# ps2_cpld_kbd.net
KiCad netlist of a schematic drawn in EAGLE
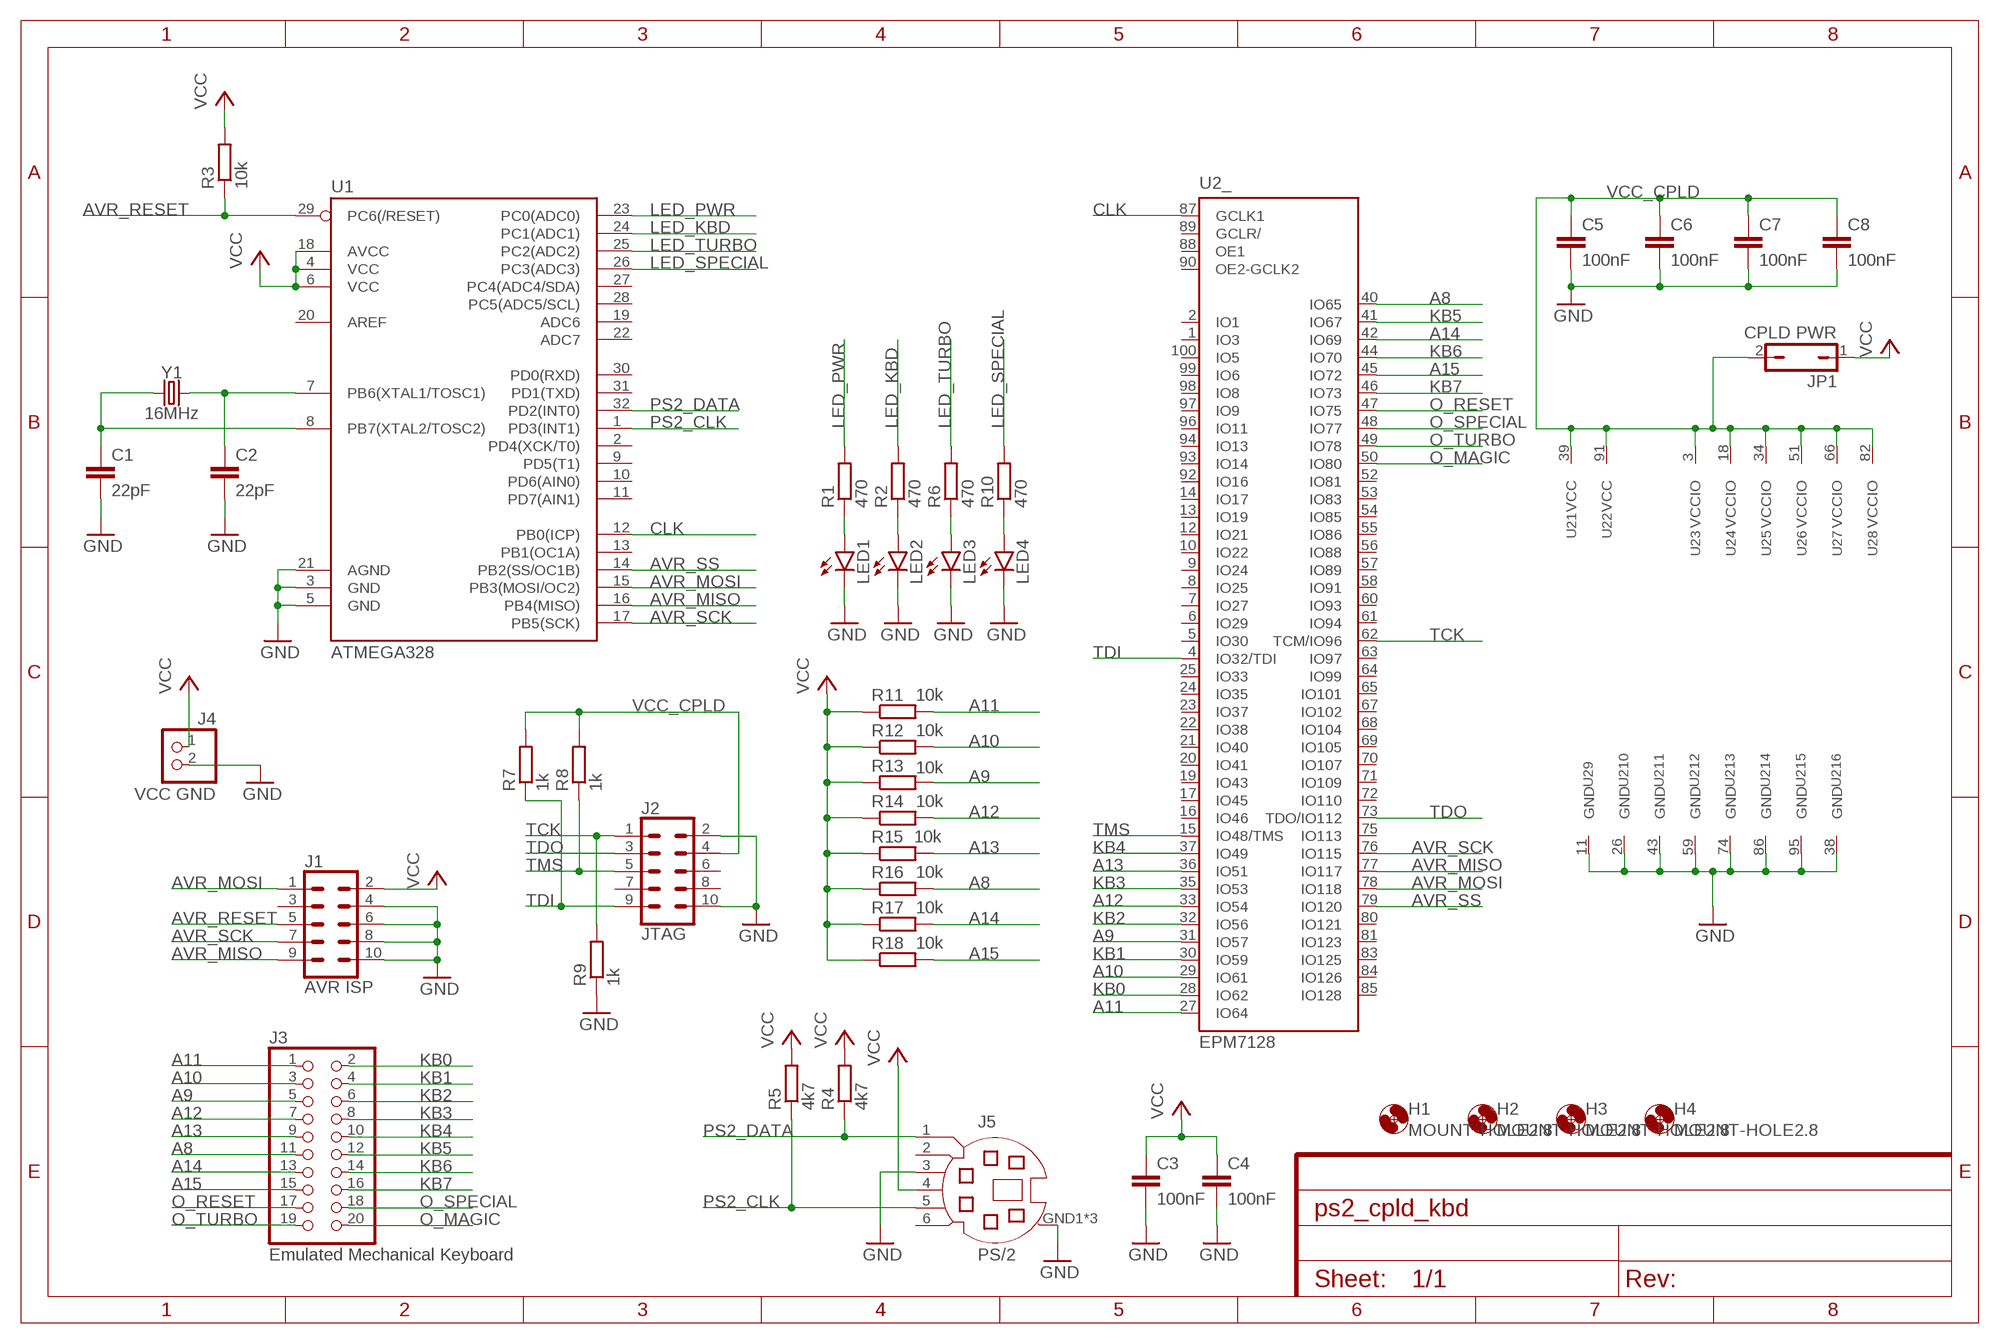
[diagram p0: schematic, sheet 1]

(export (version "E")
  (design (tool "Eeschema 10.0.6"))
  (components
    (comp (ref "C1")
      (value "22pF")
      (footprint "eagle-import:C0805K")
      (libsource (lib "eagle-import") (part "C-EUC0805K"))
    )
    (comp (ref "C2")
      (value "22pF")
      (footprint "eagle-import:C0805K")
      (libsource (lib "eagle-import") (part "C-EUC0805K"))
    )
    (comp (ref "C3")
      (value "100nF")
      (footprint "eagle-import:C0805K")
      (libsource (lib "eagle-import") (part "C-EUC0805K"))
    )
    (comp (ref "C4")
      (value "100nF")
      (footprint "eagle-import:C0805K")
      (libsource (lib "eagle-import") (part "C-EUC0805K"))
    )
    (comp (ref "C5")
      (value "100nF")
      (footprint "eagle-import:C0805K")
      (libsource (lib "eagle-import") (part "C-EUC0805K"))
    )
    (comp (ref "C6")
      (value "100nF")
      (footprint "eagle-import:C0805K")
      (libsource (lib "eagle-import") (part "C-EUC0805K"))
    )
    (comp (ref "C7")
      (value "100nF")
      (footprint "eagle-import:C0805K")
      (libsource (lib "eagle-import") (part "C-EUC0805K"))
    )
    (comp (ref "C8")
      (value "100nF")
      (footprint "eagle-import:C0805K")
      (libsource (lib "eagle-import") (part "C-EUC0805K"))
    )
    (comp (ref "H1")
      (value "MOUNT-HOLE2.8")
      (footprint "eagle-import:2,8")
      (libsource (lib "eagle-import") (part "MOUNT-HOLE2.8"))
    )
    (comp (ref "H2")
      (value "MOUNT-HOLE2.8")
      (footprint "eagle-import:2,8")
      (libsource (lib "eagle-import") (part "MOUNT-HOLE2.8"))
    )
    (comp (ref "H3")
      (value "MOUNT-HOLE2.8")
      (footprint "eagle-import:2,8")
      (libsource (lib "eagle-import") (part "MOUNT-HOLE2.8"))
    )
    (comp (ref "H4")
      (value "MOUNT-HOLE2.8")
      (footprint "eagle-import:2,8")
      (libsource (lib "eagle-import") (part "MOUNT-HOLE2.8"))
    )
    (comp (ref "J1")
      (value "AVR ISP")
      (footprint "eagle-import:2X5-SHROUDED_LOCK")
      (libsource (lib "eagle-import") (part "CONN_05X2SHD_LOCK"))
    )
    (comp (ref "J2")
      (value "JTAG")
      (footprint "eagle-import:2X5-SHROUDED_LOCK")
      (libsource (lib "eagle-import") (part "CONN_05X2SHD_LOCK"))
    )
    (comp (ref "J3")
      (value "Emulated Mechanical Keyboard")
      (footprint "eagle-import:2X10")
      (libsource (lib "eagle-import") (part "PINHD-2X10"))
    )
    (comp (ref "J4")
      (value "VCC GND")
      (footprint "eagle-import:1X02")
      (libsource (lib "eagle-import") (part "PINHD-1X2"))
    )
    (comp (ref "J5")
      (value "PS/2")
      (footprint "eagle-import:MDIN06SS")
      (libsource (lib "eagle-import") (part "MD06SS"))
    )
    (comp (ref "JP1")
      (value "CPLD PWR")
      (footprint "eagle-import:JP1")
      (libsource (lib "eagle-import") (part "JP1Q"))
    )
    (comp (ref "LED1")
      (value "LEDCHIPLED_0805")
      (footprint "eagle-import:CHIPLED_0805")
      (libsource (lib "eagle-import") (part "LEDCHIPLED_0805"))
    )
    (comp (ref "LED2")
      (value "LEDCHIPLED_0805")
      (footprint "eagle-import:CHIPLED_0805")
      (libsource (lib "eagle-import") (part "LEDCHIPLED_0805"))
    )
    (comp (ref "LED3")
      (value "LEDCHIPLED_0805")
      (footprint "eagle-import:CHIPLED_0805")
      (libsource (lib "eagle-import") (part "LEDCHIPLED_0805"))
    )
    (comp (ref "LED4")
      (value "LEDCHIPLED_0805")
      (footprint "eagle-import:CHIPLED_0805")
      (libsource (lib "eagle-import") (part "LEDCHIPLED_0805"))
    )
    (comp (ref "R1")
      (value "470")
      (footprint "eagle-import:R0805")
      (libsource (lib "eagle-import") (part "R-EU_R0805"))
    )
    (comp (ref "R2")
      (value "470")
      (footprint "eagle-import:R0805")
      (libsource (lib "eagle-import") (part "R-EU_R0805"))
    )
    (comp (ref "R3")
      (value "10k")
      (footprint "eagle-import:R0805")
      (libsource (lib "eagle-import") (part "R-EU_R0805"))
    )
    (comp (ref "R4")
      (value "4k7")
      (footprint "eagle-import:R0805")
      (libsource (lib "eagle-import") (part "R-EU_R0805"))
    )
    (comp (ref "R5")
      (value "4k7")
      (footprint "eagle-import:R0805")
      (libsource (lib "eagle-import") (part "R-EU_R0805"))
    )
    (comp (ref "R6")
      (value "470")
      (footprint "eagle-import:R0805")
      (libsource (lib "eagle-import") (part "R-EU_R0805"))
    )
    (comp (ref "R7")
      (value "1k")
      (footprint "eagle-import:R0805")
      (libsource (lib "eagle-import") (part "R-EU_R0805"))
    )
    (comp (ref "R8")
      (value "1k")
      (footprint "eagle-import:R0805")
      (libsource (lib "eagle-import") (part "R-EU_R0805"))
    )
    (comp (ref "R9")
      (value "1k")
      (footprint "eagle-import:R0805")
      (libsource (lib "eagle-import") (part "R-EU_R0805"))
    )
    (comp (ref "R10")
      (value "470")
      (footprint "eagle-import:R0805")
      (libsource (lib "eagle-import") (part "R-EU_R0805"))
    )
    (comp (ref "R11")
      (value "10k")
      (footprint "eagle-import:R0805")
      (libsource (lib "eagle-import") (part "R-EU_R0805"))
    )
    (comp (ref "R12")
      (value "10k")
      (footprint "eagle-import:R0805")
      (libsource (lib "eagle-import") (part "R-EU_R0805"))
    )
    (comp (ref "R13")
      (value "10k")
      (footprint "eagle-import:R0805")
      (libsource (lib "eagle-import") (part "R-EU_R0805"))
    )
    (comp (ref "R14")
      (value "10k")
      (footprint "eagle-import:R0805")
      (libsource (lib "eagle-import") (part "R-EU_R0805"))
    )
    (comp (ref "R15")
      (value "10k")
      (footprint "eagle-import:R0805")
      (libsource (lib "eagle-import") (part "R-EU_R0805"))
    )
    (comp (ref "R16")
      (value "10k")
      (footprint "eagle-import:R0805")
      (libsource (lib "eagle-import") (part "R-EU_R0805"))
    )
    (comp (ref "R17")
      (value "10k")
      (footprint "eagle-import:R0805")
      (libsource (lib "eagle-import") (part "R-EU_R0805"))
    )
    (comp (ref "R18")
      (value "10k")
      (footprint "eagle-import:R0805")
      (libsource (lib "eagle-import") (part "R-EU_R0805"))
    )
    (comp (ref "U1")
      (value "ATMEGA328")
      (footprint "eagle-import:TQFP32-08")
      (libsource (lib "eagle-import") (part "ATMEGA328P_TQFP"))
    )
    (comp (ref "U2")
      (value "EPM7128")
      (footprint "eagle-import:TQFP100")
      (fields (field (name "MPN") "EPM7128STC100-7N"))
      (libsource (lib "eagle-import") (part "EPM7128-?100T"))
    )
    (comp (ref "Y1")
      (value "16MHz")
      (footprint "eagle-import:HC49US")
      (libsource (lib "eagle-import") (part "CRYSTAL-16MHZPTH-HC49US"))
    )
  )
  (nets
    (net (code "1") (name "/A8") (class "Default")
      (node (ref "J3") (pin "11") (pinfunction "11_11") (pintype "passive"))
      (node (ref "R16") (pin "2") (pinfunction "2_2") (pintype "passive"))
      (node (ref "U2") (pin "40") (pinfunction "IO65_40") (pintype "bidirectional"))
    )
    (net (code "2") (name "/A9") (class "Default")
      (node (ref "J3") (pin "5") (pinfunction "5_5") (pintype "passive"))
      (node (ref "R13") (pin "2") (pinfunction "2_2") (pintype "passive"))
      (node (ref "U2") (pin "31") (pinfunction "IO57_31") (pintype "bidirectional"))
    )
    (net (code "3") (name "/A10") (class "Default")
      (node (ref "J3") (pin "3") (pinfunction "3_3") (pintype "passive"))
      (node (ref "R12") (pin "2") (pinfunction "2_2") (pintype "passive"))
      (node (ref "U2") (pin "29") (pinfunction "IO61_29") (pintype "bidirectional"))
    )
    (net (code "4") (name "/A11") (class "Default")
      (node (ref "J3") (pin "1") (pinfunction "1_1") (pintype "passive"))
      (node (ref "R11") (pin "2") (pinfunction "2_2") (pintype "passive"))
      (node (ref "U2") (pin "27") (pinfunction "IO64_27") (pintype "bidirectional"))
    )
    (net (code "5") (name "/A12") (class "Default")
      (node (ref "J3") (pin "7") (pinfunction "7_7") (pintype "passive"))
      (node (ref "R14") (pin "2") (pinfunction "2_2") (pintype "passive"))
      (node (ref "U2") (pin "33") (pinfunction "IO54_33") (pintype "bidirectional"))
    )
    (net (code "6") (name "/A13") (class "Default")
      (node (ref "J3") (pin "9") (pinfunction "9_9") (pintype "passive"))
      (node (ref "R15") (pin "2") (pinfunction "2_2") (pintype "passive"))
      (node (ref "U2") (pin "36") (pinfunction "IO51_36") (pintype "bidirectional"))
    )
    (net (code "7") (name "/A14") (class "Default")
      (node (ref "J3") (pin "13") (pinfunction "13_13") (pintype "passive"))
      (node (ref "R17") (pin "2") (pinfunction "2_2") (pintype "passive"))
      (node (ref "U2") (pin "42") (pinfunction "IO69_42") (pintype "bidirectional"))
    )
    (net (code "8") (name "/A15") (class "Default")
      (node (ref "J3") (pin "15") (pinfunction "15_15") (pintype "passive"))
      (node (ref "R18") (pin "2") (pinfunction "2_2") (pintype "passive"))
      (node (ref "U2") (pin "45") (pinfunction "IO72_45") (pintype "bidirectional"))
    )
    (net (code "9") (name "/AVR_MISO") (class "Default")
      (node (ref "J1") (pin "9") (pinfunction "9_9") (pintype "passive"))
      (node (ref "U1") (pin "16") (pinfunction "PB4(MISO)_16") (pintype "bidirectional"))
      (node (ref "U2") (pin "77") (pinfunction "IO117_77") (pintype "bidirectional"))
    )
    (net (code "10") (name "/AVR_MOSI") (class "Default")
      (node (ref "J1") (pin "1") (pinfunction "1_1") (pintype "passive"))
      (node (ref "U1") (pin "15") (pinfunction "PB3(MOSI/OC2)_15") (pintype "bidirectional"))
      (node (ref "U2") (pin "78") (pinfunction "IO118_78") (pintype "bidirectional"))
    )
    (net (code "11") (name "/AVR_RESET") (class "Default")
      (node (ref "J1") (pin "5") (pinfunction "5_5") (pintype "passive"))
      (node (ref "R3") (pin "1") (pinfunction "1_1") (pintype "passive"))
      (node (ref "U1") (pin "29") (pinfunction "PC6(/RESET)_29") (pintype "bidirectional"))
    )
    (net (code "12") (name "/AVR_SCK") (class "Default")
      (node (ref "J1") (pin "7") (pinfunction "7_7") (pintype "passive"))
      (node (ref "U1") (pin "17") (pinfunction "PB5(SCK)_17") (pintype "bidirectional"))
      (node (ref "U2") (pin "76") (pinfunction "IO115_76") (pintype "bidirectional"))
    )
    (net (code "13") (name "/AVR_SS") (class "Default")
      (node (ref "U1") (pin "14") (pinfunction "PB2(SS/OC1B)_14") (pintype "bidirectional"))
      (node (ref "U2") (pin "79") (pinfunction "IO120_79") (pintype "bidirectional"))
    )
    (net (code "14") (name "/CLK") (class "Default")
      (node (ref "U1") (pin "12") (pinfunction "PB0(ICP)_12") (pintype "bidirectional"))
      (node (ref "U2") (pin "87") (pinfunction "GCLK1_87") (pintype "input"))
    )
    (net (code "15") (name "/KB0") (class "Default")
      (node (ref "J3") (pin "2") (pinfunction "2_2") (pintype "passive"))
      (node (ref "U2") (pin "28") (pinfunction "IO62_28") (pintype "bidirectional"))
    )
    (net (code "16") (name "/KB1") (class "Default")
      (node (ref "J3") (pin "4") (pinfunction "4_4") (pintype "passive"))
      (node (ref "U2") (pin "30") (pinfunction "IO59_30") (pintype "bidirectional"))
    )
    (net (code "17") (name "/KB2") (class "Default")
      (node (ref "J3") (pin "6") (pinfunction "6_6") (pintype "passive"))
      (node (ref "U2") (pin "32") (pinfunction "IO56_32") (pintype "bidirectional"))
    )
    (net (code "18") (name "/KB3") (class "Default")
      (node (ref "J3") (pin "8") (pinfunction "8_8") (pintype "passive"))
      (node (ref "U2") (pin "35") (pinfunction "IO53_35") (pintype "bidirectional"))
    )
    (net (code "19") (name "/KB4") (class "Default")
      (node (ref "J3") (pin "10") (pinfunction "10_10") (pintype "passive"))
      (node (ref "U2") (pin "37") (pinfunction "IO49_37") (pintype "bidirectional"))
    )
    (net (code "20") (name "/KB5") (class "Default")
      (node (ref "J3") (pin "12") (pinfunction "12_12") (pintype "passive"))
      (node (ref "U2") (pin "41") (pinfunction "IO67_41") (pintype "bidirectional"))
    )
    (net (code "21") (name "/KB6") (class "Default")
      (node (ref "J3") (pin "14") (pinfunction "14_14") (pintype "passive"))
      (node (ref "U2") (pin "44") (pinfunction "IO70_44") (pintype "bidirectional"))
    )
    (net (code "22") (name "/KB7") (class "Default")
      (node (ref "J3") (pin "16") (pinfunction "16_16") (pintype "passive"))
      (node (ref "U2") (pin "46") (pinfunction "IO73_46") (pintype "bidirectional"))
    )
    (net (code "23") (name "/LED_KBD") (class "Default")
      (node (ref "R2") (pin "2") (pinfunction "2_2") (pintype "passive"))
      (node (ref "U1") (pin "24") (pinfunction "PC1(ADC1)_24") (pintype "bidirectional"))
    )
    (net (code "24") (name "/LED_PWR") (class "Default")
      (node (ref "R1") (pin "2") (pinfunction "2_2") (pintype "passive"))
      (node (ref "U1") (pin "23") (pinfunction "PC0(ADC0)_23") (pintype "bidirectional"))
    )
    (net (code "25") (name "/LED_SPECIAL") (class "Default")
      (node (ref "R10") (pin "2") (pinfunction "2_2") (pintype "passive"))
      (node (ref "U1") (pin "26") (pinfunction "PC3(ADC3)_26") (pintype "bidirectional"))
    )
    (net (code "26") (name "/LED_TURBO") (class "Default")
      (node (ref "R6") (pin "2") (pinfunction "2_2") (pintype "passive"))
      (node (ref "U1") (pin "25") (pinfunction "PC2(ADC2)_25") (pintype "bidirectional"))
    )
    (net (code "27") (name "/O_MAGIC") (class "Default")
      (node (ref "J3") (pin "20") (pinfunction "20_20") (pintype "passive"))
      (node (ref "U2") (pin "50") (pinfunction "IO80_50") (pintype "bidirectional"))
    )
    (net (code "28") (name "/O_RESET") (class "Default")
      (node (ref "J3") (pin "17") (pinfunction "17_17") (pintype "passive"))
      (node (ref "U2") (pin "47") (pinfunction "IO75_47") (pintype "bidirectional"))
    )
    (net (code "29") (name "/O_SPECIAL") (class "Default")
      (node (ref "J3") (pin "18") (pinfunction "18_18") (pintype "passive"))
      (node (ref "U2") (pin "48") (pinfunction "IO77_48") (pintype "bidirectional"))
    )
    (net (code "30") (name "/O_TURBO") (class "Default")
      (node (ref "J3") (pin "19") (pinfunction "19_19") (pintype "passive"))
      (node (ref "U2") (pin "49") (pinfunction "IO78_49") (pintype "bidirectional"))
    )
    (net (code "31") (name "/PS2_CLK") (class "Default")
      (node (ref "J5") (pin "5") (pinfunction "5_5") (pintype "passive"))
      (node (ref "R5") (pin "1") (pinfunction "1_1") (pintype "passive"))
      (node (ref "U1") (pin "1") (pinfunction "PD3(INT1)_1") (pintype "bidirectional"))
    )
    (net (code "32") (name "/PS2_DATA") (class "Default")
      (node (ref "J5") (pin "1") (pinfunction "1_1") (pintype "passive"))
      (node (ref "R4") (pin "1") (pinfunction "1_1") (pintype "passive"))
      (node (ref "U1") (pin "32") (pinfunction "PD2(INT0)_32") (pintype "bidirectional"))
    )
    (net (code "33") (name "/TCK") (class "Default")
      (node (ref "J2") (pin "1") (pinfunction "1_1") (pintype "passive"))
      (node (ref "R9") (pin "2") (pinfunction "2_2") (pintype "passive"))
      (node (ref "U2") (pin "62") (pinfunction "TCM/IO96_62") (pintype "bidirectional"))
    )
    (net (code "34") (name "/TDI") (class "Default")
      (node (ref "J2") (pin "9") (pinfunction "9_9") (pintype "passive"))
      (node (ref "R7") (pin "1") (pinfunction "1_1") (pintype "passive"))
      (node (ref "U2") (pin "4") (pinfunction "IO32/TDI_4") (pintype "bidirectional"))
    )
    (net (code "35") (name "/TDO") (class "Default")
      (node (ref "J2") (pin "3") (pinfunction "3_3") (pintype "passive"))
      (node (ref "U2") (pin "73") (pinfunction "TDO/IO112_73") (pintype "bidirectional"))
    )
    (net (code "36") (name "/TMS") (class "Default")
      (node (ref "J2") (pin "5") (pinfunction "5_5") (pintype "passive"))
      (node (ref "R8") (pin "1") (pinfunction "1_1") (pintype "passive"))
      (node (ref "U2") (pin "15") (pinfunction "IO48/TMS_15") (pintype "bidirectional"))
    )
    (net (code "37") (name "/VCC_CPLD") (class "Default")
      (node (ref "C5") (pin "1") (pinfunction "1_1") (pintype "passive"))
      (node (ref "C6") (pin "1") (pinfunction "1_1") (pintype "passive"))
      (node (ref "C7") (pin "1") (pinfunction "1_1") (pintype "passive"))
      (node (ref "C8") (pin "1") (pinfunction "1_1") (pintype "passive"))
      (node (ref "J2") (pin "4") (pinfunction "4_4") (pintype "passive"))
      (node (ref "JP1") (pin "2") (pinfunction "2_2") (pintype "passive"))
      (node (ref "R7") (pin "2") (pinfunction "2_2") (pintype "passive"))
      (node (ref "R8") (pin "2") (pinfunction "2_2") (pintype "passive"))
      (node (ref "U2") (pin "18") (pinfunction "VCCIO_18") (pintype "power_in"))
      (node (ref "U2") (pin "3") (pinfunction "VCCIO_3") (pintype "power_in"))
      (node (ref "U2") (pin "34") (pinfunction "VCCIO_34") (pintype "power_in"))
      (node (ref "U2") (pin "39") (pinfunction "VCC_39") (pintype "power_in"))
      (node (ref "U2") (pin "51") (pinfunction "VCCIO_51") (pintype "power_in"))
      (node (ref "U2") (pin "66") (pinfunction "VCCIO_66") (pintype "power_in"))
      (node (ref "U2") (pin "82") (pinfunction "VCCIO_82") (pintype "power_in"))
      (node (ref "U2") (pin "91") (pinfunction "VCC_91") (pintype "power_in"))
    )
    (net (code "38") (name "GND") (class "Default")
      (node (ref "C1") (pin "2") (pinfunction "2_2") (pintype "passive"))
      (node (ref "C2") (pin "2") (pinfunction "2_2") (pintype "passive"))
      (node (ref "C3") (pin "2") (pinfunction "2_2") (pintype "passive"))
      (node (ref "C4") (pin "2") (pinfunction "2_2") (pintype "passive"))
      (node (ref "C5") (pin "2") (pinfunction "2_2") (pintype "passive"))
      (node (ref "C6") (pin "2") (pinfunction "2_2") (pintype "passive"))
      (node (ref "C7") (pin "2") (pinfunction "2_2") (pintype "passive"))
      (node (ref "C8") (pin "2") (pinfunction "2_2") (pintype "passive"))
      (node (ref "J1") (pin "10") (pinfunction "10_10") (pintype "passive"))
      (node (ref "J1") (pin "4") (pinfunction "4_4") (pintype "passive"))
      (node (ref "J1") (pin "6") (pinfunction "6_6") (pintype "passive"))
      (node (ref "J1") (pin "8") (pinfunction "8_8") (pintype "passive"))
      (node (ref "J2") (pin "10") (pinfunction "10_10") (pintype "passive"))
      (node (ref "J2") (pin "2") (pinfunction "2_2") (pintype "passive"))
      (node (ref "J4") (pin "2") (pinfunction "2_2") (pintype "passive"))
      (node (ref "J5") (pin "3") (pinfunction "3_3") (pintype "passive"))
      (node (ref "J5") (pin "GND1") (pinfunction "GND_GND1") (pintype "power_in"))
      (node (ref "J5") (pin "GND2") (pinfunction "GND_GND2") (pintype "power_in"))
      (node (ref "J5") (pin "GND3") (pinfunction "GND_GND3") (pintype "power_in"))
      (node (ref "LED1") (pin "C") (pinfunction "C_C") (pintype "passive"))
      (node (ref "LED2") (pin "C") (pinfunction "C_C") (pintype "passive"))
      (node (ref "LED3") (pin "C") (pinfunction "C_C") (pintype "passive"))
      (node (ref "LED4") (pin "C") (pinfunction "C_C") (pintype "passive"))
      (node (ref "R9") (pin "1") (pinfunction "1_1") (pintype "passive"))
      (node (ref "U1") (pin "21") (pinfunction "AGND_21") (pintype "bidirectional"))
      (node (ref "U1") (pin "3") (pinfunction "GND_3") (pintype "bidirectional"))
      (node (ref "U1") (pin "5") (pinfunction "GND_5") (pintype "bidirectional"))
      (node (ref "U2") (pin "11") (pinfunction "GND_11") (pintype "power_in"))
      (node (ref "U2") (pin "26") (pinfunction "GND_26") (pintype "power_in"))
      (node (ref "U2") (pin "38") (pinfunction "GND_38") (pintype "power_in"))
      (node (ref "U2") (pin "43") (pinfunction "GND_43") (pintype "power_in"))
      (node (ref "U2") (pin "59") (pinfunction "GND_59") (pintype "power_in"))
      (node (ref "U2") (pin "74") (pinfunction "GND_74") (pintype "power_in"))
      (node (ref "U2") (pin "86") (pinfunction "GND_86") (pintype "power_in"))
      (node (ref "U2") (pin "95") (pinfunction "GND_95") (pintype "power_in"))
    )
    (net (code "39") (name "Net-(LED1-PadA)") (class "Default")
      (node (ref "LED1") (pin "A") (pinfunction "A_A") (pintype "passive"))
      (node (ref "R1") (pin "1") (pinfunction "1_1") (pintype "passive"))
    )
    (net (code "40") (name "Net-(LED2-PadA)") (class "Default")
      (node (ref "LED2") (pin "A") (pinfunction "A_A") (pintype "passive"))
      (node (ref "R2") (pin "1") (pinfunction "1_1") (pintype "passive"))
    )
    (net (code "41") (name "Net-(LED3-PadA)") (class "Default")
      (node (ref "LED3") (pin "A") (pinfunction "A_A") (pintype "passive"))
      (node (ref "R6") (pin "1") (pinfunction "1_1") (pintype "passive"))
    )
    (net (code "42") (name "Net-(LED4-PadA)") (class "Default")
      (node (ref "LED4") (pin "A") (pinfunction "A_A") (pintype "passive"))
      (node (ref "R10") (pin "1") (pinfunction "1_1") (pintype "passive"))
    )
    (net (code "43") (name "Net-(U1-PB6(XTAL1{slash}TOSC1))") (class "Default")
      (node (ref "C2") (pin "1") (pinfunction "1_1") (pintype "passive"))
      (node (ref "U1") (pin "7") (pinfunction "PB6(XTAL1/TOSC1)_7") (pintype "bidirectional"))
      (node (ref "Y1") (pin "2") (pinfunction "2_2") (pintype "passive"))
    )
    (net (code "44") (name "Net-(U1-PB7(XTAL2{slash}TOSC2))") (class "Default")
      (node (ref "C1") (pin "1") (pinfunction "1_1") (pintype "passive"))
      (node (ref "U1") (pin "8") (pinfunction "PB7(XTAL2/TOSC2)_8") (pintype "bidirectional"))
      (node (ref "Y1") (pin "1") (pinfunction "1_1") (pintype "passive"))
    )
    (net (code "45") (name "VCC") (class "Default")
      (node (ref "C3") (pin "1") (pinfunction "1_1") (pintype "passive"))
      (node (ref "C4") (pin "1") (pinfunction "1_1") (pintype "passive"))
      (node (ref "J1") (pin "2") (pinfunction "2_2") (pintype "passive"))
      (node (ref "J4") (pin "1") (pinfunction "1_1") (pintype "passive"))
      (node (ref "J5") (pin "4") (pinfunction "4_4") (pintype "passive"))
      (node (ref "JP1") (pin "1") (pinfunction "1_1") (pintype "passive"))
      (node (ref "R11") (pin "1") (pinfunction "1_1") (pintype "passive"))
      (node (ref "R12") (pin "1") (pinfunction "1_1") (pintype "passive"))
      (node (ref "R13") (pin "1") (pinfunction "1_1") (pintype "passive"))
      (node (ref "R14") (pin "1") (pinfunction "1_1") (pintype "passive"))
      (node (ref "R15") (pin "1") (pinfunction "1_1") (pintype "passive"))
      (node (ref "R16") (pin "1") (pinfunction "1_1") (pintype "passive"))
      (node (ref "R17") (pin "1") (pinfunction "1_1") (pintype "passive"))
      (node (ref "R18") (pin "1") (pinfunction "1_1") (pintype "passive"))
      (node (ref "R3") (pin "2") (pinfunction "2_2") (pintype "passive"))
      (node (ref "R4") (pin "2") (pinfunction "2_2") (pintype "passive"))
      (node (ref "R5") (pin "2") (pinfunction "2_2") (pintype "passive"))
      (node (ref "U1") (pin "18") (pinfunction "AVCC_18") (pintype "bidirectional"))
      (node (ref "U1") (pin "4") (pinfunction "VCC_4") (pintype "bidirectional"))
      (node (ref "U1") (pin "6") (pinfunction "VCC_6") (pintype "bidirectional"))
    )
    (net (code "46") (name "unconnected-(J1-Pad3)") (class "Default")
      (node (ref "J1") (pin "3") (pinfunction "3_3") (pintype "passive"))
    )
    (net (code "47") (name "unconnected-(J2-Pad6)") (class "Default")
      (node (ref "J2") (pin "6") (pinfunction "6_6") (pintype "passive"))
    )
    (net (code "48") (name "unconnected-(J2-Pad7)") (class "Default")
      (node (ref "J2") (pin "7") (pinfunction "7_7") (pintype "passive"))
    )
    (net (code "49") (name "unconnected-(J2-Pad8)") (class "Default")
      (node (ref "J2") (pin "8") (pinfunction "8_8") (pintype "passive"))
    )
    (net (code "50") (name "unconnected-(J5-Pad2)") (class "Default")
      (node (ref "J5") (pin "2") (pinfunction "2_2") (pintype "passive"))
    )
    (net (code "51") (name "unconnected-(J5-Pad6)") (class "Default")
      (node (ref "J5") (pin "6") (pinfunction "6_6") (pintype "passive"))
    )
    (net (code "52") (name "unconnected-(U1-ADC6-Pad19)") (class "Default")
      (node (ref "U1") (pin "19") (pinfunction "ADC6_19") (pintype "bidirectional"))
    )
    (net (code "53") (name "unconnected-(U1-ADC7-Pad22)") (class "Default")
      (node (ref "U1") (pin "22") (pinfunction "ADC7_22") (pintype "bidirectional"))
    )
    (net (code "54") (name "unconnected-(U1-AREF-Pad20)") (class "Default")
      (node (ref "U1") (pin "20") (pinfunction "AREF_20") (pintype "bidirectional"))
    )
    (net (code "55") (name "unconnected-(U1-PB1(OC1A)-Pad13)") (class "Default")
      (node (ref "U1") (pin "13") (pinfunction "PB1(OC1A)_13") (pintype "bidirectional"))
    )
    (net (code "56") (name "unconnected-(U1-PC4(ADC4{slash}SDA)-Pad27)") (class "Default")
      (node (ref "U1") (pin "27") (pinfunction "PC4(ADC4/SDA)_27") (pintype "bidirectional"))
    )
    (net (code "57") (name "unconnected-(U1-PC5(ADC5{slash}SCL)-Pad28)") (class "Default")
      (node (ref "U1") (pin "28") (pinfunction "PC5(ADC5/SCL)_28") (pintype "bidirectional"))
    )
    (net (code "58") (name "unconnected-(U1-PD0(RXD)-Pad30)") (class "Default")
      (node (ref "U1") (pin "30") (pinfunction "PD0(RXD)_30") (pintype "bidirectional"))
    )
    (net (code "59") (name "unconnected-(U1-PD1(TXD)-Pad31)") (class "Default")
      (node (ref "U1") (pin "31") (pinfunction "PD1(TXD)_31") (pintype "bidirectional"))
    )
    (net (code "60") (name "unconnected-(U1-PD4(XCK{slash}T0)-Pad2)") (class "Default")
      (node (ref "U1") (pin "2") (pinfunction "PD4(XCK/T0)_2") (pintype "bidirectional"))
    )
    (net (code "61") (name "unconnected-(U1-PD5(T1)-Pad9)") (class "Default")
      (node (ref "U1") (pin "9") (pinfunction "PD5(T1)_9") (pintype "bidirectional"))
    )
    (net (code "62") (name "unconnected-(U1-PD6(AIN0)-Pad10)") (class "Default")
      (node (ref "U1") (pin "10") (pinfunction "PD6(AIN0)_10") (pintype "bidirectional"))
    )
    (net (code "63") (name "unconnected-(U1-PD7(AIN1)-Pad11)") (class "Default")
      (node (ref "U1") (pin "11") (pinfunction "PD7(AIN1)_11") (pintype "bidirectional"))
    )
    (net (code "64") (name "unconnected-(U2Q-GCLR{slash}-Pad89)") (class "Default")
      (node (ref "U2") (pin "89") (pinfunction "GCLR/_89") (pintype "input"))
    )
    (net (code "65") (name "unconnected-(U2Q-IO1-Pad2)") (class "Default")
      (node (ref "U2") (pin "2") (pinfunction "IO1_2") (pintype "bidirectional"))
    )
    (net (code "66") (name "unconnected-(U2Q-IO3-Pad1)") (class "Default")
      (node (ref "U2") (pin "1") (pinfunction "IO3_1") (pintype "bidirectional"))
    )
    (net (code "67") (name "unconnected-(U2Q-IO5-Pad100)") (class "Default")
      (node (ref "U2") (pin "100") (pinfunction "IO5_100") (pintype "bidirectional"))
    )
    (net (code "68") (name "unconnected-(U2Q-IO6-Pad99)") (class "Default")
      (node (ref "U2") (pin "99") (pinfunction "IO6_99") (pintype "bidirectional"))
    )
    (net (code "69") (name "unconnected-(U2Q-IO8-Pad98)") (class "Default")
      (node (ref "U2") (pin "98") (pinfunction "IO8_98") (pintype "bidirectional"))
    )
    (net (code "70") (name "unconnected-(U2Q-IO9-Pad97)") (class "Default")
      (node (ref "U2") (pin "97") (pinfunction "IO9_97") (pintype "bidirectional"))
    )
    (net (code "71") (name "unconnected-(U2Q-IO11-Pad96)") (class "Default")
      (node (ref "U2") (pin "96") (pinfunction "IO11_96") (pintype "bidirectional"))
    )
    (net (code "72") (name "unconnected-(U2Q-IO13-Pad94)") (class "Default")
      (node (ref "U2") (pin "94") (pinfunction "IO13_94") (pintype "bidirectional"))
    )
    (net (code "73") (name "unconnected-(U2Q-IO14-Pad93)") (class "Default")
      (node (ref "U2") (pin "93") (pinfunction "IO14_93") (pintype "bidirectional"))
    )
    (net (code "74") (name "unconnected-(U2Q-IO16-Pad92)") (class "Default")
      (node (ref "U2") (pin "92") (pinfunction "IO16_92") (pintype "bidirectional"))
    )
    (net (code "75") (name "unconnected-(U2Q-IO17-Pad14)") (class "Default")
      (node (ref "U2") (pin "14") (pinfunction "IO17_14") (pintype "bidirectional"))
    )
    (net (code "76") (name "unconnected-(U2Q-IO19-Pad13)") (class "Default")
      (node (ref "U2") (pin "13") (pinfunction "IO19_13") (pintype "bidirectional"))
    )
    (net (code "77") (name "unconnected-(U2Q-IO21-Pad12)") (class "Default")
      (node (ref "U2") (pin "12") (pinfunction "IO21_12") (pintype "bidirectional"))
    )
    (net (code "78") (name "unconnected-(U2Q-IO22-Pad10)") (class "Default")
      (node (ref "U2") (pin "10") (pinfunction "IO22_10") (pintype "bidirectional"))
    )
    (net (code "79") (name "unconnected-(U2Q-IO24-Pad9)") (class "Default")
      (node (ref "U2") (pin "9") (pinfunction "IO24_9") (pintype "bidirectional"))
    )
    (net (code "80") (name "unconnected-(U2Q-IO25-Pad8)") (class "Default")
      (node (ref "U2") (pin "8") (pinfunction "IO25_8") (pintype "bidirectional"))
    )
    (net (code "81") (name "unconnected-(U2Q-IO27-Pad7)") (class "Default")
      (node (ref "U2") (pin "7") (pinfunction "IO27_7") (pintype "bidirectional"))
    )
    (net (code "82") (name "unconnected-(U2Q-IO29-Pad6)") (class "Default")
      (node (ref "U2") (pin "6") (pinfunction "IO29_6") (pintype "bidirectional"))
    )
    (net (code "83") (name "unconnected-(U2Q-IO30-Pad5)") (class "Default")
      (node (ref "U2") (pin "5") (pinfunction "IO30_5") (pintype "bidirectional"))
    )
    (net (code "84") (name "unconnected-(U2Q-IO33-Pad25)") (class "Default")
      (node (ref "U2") (pin "25") (pinfunction "IO33_25") (pintype "bidirectional"))
    )
    (net (code "85") (name "unconnected-(U2Q-IO35-Pad24)") (class "Default")
      (node (ref "U2") (pin "24") (pinfunction "IO35_24") (pintype "bidirectional"))
    )
    (net (code "86") (name "unconnected-(U2Q-IO37-Pad23)") (class "Default")
      (node (ref "U2") (pin "23") (pinfunction "IO37_23") (pintype "bidirectional"))
    )
    (net (code "87") (name "unconnected-(U2Q-IO38-Pad22)") (class "Default")
      (node (ref "U2") (pin "22") (pinfunction "IO38_22") (pintype "bidirectional"))
    )
    (net (code "88") (name "unconnected-(U2Q-IO40-Pad21)") (class "Default")
      (node (ref "U2") (pin "21") (pinfunction "IO40_21") (pintype "bidirectional"))
    )
    (net (code "89") (name "unconnected-(U2Q-IO41-Pad20)") (class "Default")
      (node (ref "U2") (pin "20") (pinfunction "IO41_20") (pintype "bidirectional"))
    )
    (net (code "90") (name "unconnected-(U2Q-IO43-Pad19)") (class "Default")
      (node (ref "U2") (pin "19") (pinfunction "IO43_19") (pintype "bidirectional"))
    )
    (net (code "91") (name "unconnected-(U2Q-IO45-Pad17)") (class "Default")
      (node (ref "U2") (pin "17") (pinfunction "IO45_17") (pintype "bidirectional"))
    )
    (net (code "92") (name "unconnected-(U2Q-IO46-Pad16)") (class "Default")
      (node (ref "U2") (pin "16") (pinfunction "IO46_16") (pintype "bidirectional"))
    )
    (net (code "93") (name "unconnected-(U2Q-IO81-Pad52)") (class "Default")
      (node (ref "U2") (pin "52") (pinfunction "IO81_52") (pintype "bidirectional"))
    )
    (net (code "94") (name "unconnected-(U2Q-IO83-Pad53)") (class "Default")
      (node (ref "U2") (pin "53") (pinfunction "IO83_53") (pintype "bidirectional"))
    )
    (net (code "95") (name "unconnected-(U2Q-IO85-Pad54)") (class "Default")
      (node (ref "U2") (pin "54") (pinfunction "IO85_54") (pintype "bidirectional"))
    )
    (net (code "96") (name "unconnected-(U2Q-IO86-Pad55)") (class "Default")
      (node (ref "U2") (pin "55") (pinfunction "IO86_55") (pintype "bidirectional"))
    )
    (net (code "97") (name "unconnected-(U2Q-IO88-Pad56)") (class "Default")
      (node (ref "U2") (pin "56") (pinfunction "IO88_56") (pintype "bidirectional"))
    )
    (net (code "98") (name "unconnected-(U2Q-IO89-Pad57)") (class "Default")
      (node (ref "U2") (pin "57") (pinfunction "IO89_57") (pintype "bidirectional"))
    )
    (net (code "99") (name "unconnected-(U2Q-IO91-Pad58)") (class "Default")
      (node (ref "U2") (pin "58") (pinfunction "IO91_58") (pintype "bidirectional"))
    )
    (net (code "100") (name "unconnected-(U2Q-IO93-Pad60)") (class "Default")
      (node (ref "U2") (pin "60") (pinfunction "IO93_60") (pintype "bidirectional"))
    )
    (net (code "101") (name "unconnected-(U2Q-IO94-Pad61)") (class "Default")
      (node (ref "U2") (pin "61") (pinfunction "IO94_61") (pintype "bidirectional"))
    )
    (net (code "102") (name "unconnected-(U2Q-IO97-Pad63)") (class "Default")
      (node (ref "U2") (pin "63") (pinfunction "IO97_63") (pintype "bidirectional"))
    )
    (net (code "103") (name "unconnected-(U2Q-IO99-Pad64)") (class "Default")
      (node (ref "U2") (pin "64") (pinfunction "IO99_64") (pintype "bidirectional"))
    )
    (net (code "104") (name "unconnected-(U2Q-IO101-Pad65)") (class "Default")
      (node (ref "U2") (pin "65") (pinfunction "IO101_65") (pintype "bidirectional"))
    )
    (net (code "105") (name "unconnected-(U2Q-IO102-Pad67)") (class "Default")
      (node (ref "U2") (pin "67") (pinfunction "IO102_67") (pintype "bidirectional"))
    )
    (net (code "106") (name "unconnected-(U2Q-IO104-Pad68)") (class "Default")
      (node (ref "U2") (pin "68") (pinfunction "IO104_68") (pintype "bidirectional"))
    )
    (net (code "107") (name "unconnected-(U2Q-IO105-Pad69)") (class "Default")
      (node (ref "U2") (pin "69") (pinfunction "IO105_69") (pintype "bidirectional"))
    )
    (net (code "108") (name "unconnected-(U2Q-IO107-Pad70)") (class "Default")
      (node (ref "U2") (pin "70") (pinfunction "IO107_70") (pintype "bidirectional"))
    )
    (net (code "109") (name "unconnected-(U2Q-IO109-Pad71)") (class "Default")
      (node (ref "U2") (pin "71") (pinfunction "IO109_71") (pintype "bidirectional"))
    )
    (net (code "110") (name "unconnected-(U2Q-IO110-Pad72)") (class "Default")
      (node (ref "U2") (pin "72") (pinfunction "IO110_72") (pintype "bidirectional"))
    )
    (net (code "111") (name "unconnected-(U2Q-IO113-Pad75)") (class "Default")
      (node (ref "U2") (pin "75") (pinfunction "IO113_75") (pintype "bidirectional"))
    )
    (net (code "112") (name "unconnected-(U2Q-IO121-Pad80)") (class "Default")
      (node (ref "U2") (pin "80") (pinfunction "IO121_80") (pintype "bidirectional"))
    )
    (net (code "113") (name "unconnected-(U2Q-IO123-Pad81)") (class "Default")
      (node (ref "U2") (pin "81") (pinfunction "IO123_81") (pintype "bidirectional"))
    )
    (net (code "114") (name "unconnected-(U2Q-IO125-Pad83)") (class "Default")
      (node (ref "U2") (pin "83") (pinfunction "IO125_83") (pintype "bidirectional"))
    )
    (net (code "115") (name "unconnected-(U2Q-IO126-Pad84)") (class "Default")
      (node (ref "U2") (pin "84") (pinfunction "IO126_84") (pintype "bidirectional"))
    )
    (net (code "116") (name "unconnected-(U2Q-IO128-Pad85)") (class "Default")
      (node (ref "U2") (pin "85") (pinfunction "IO128_85") (pintype "bidirectional"))
    )
    (net (code "117") (name "unconnected-(U2Q-OE1-Pad88)") (class "Default")
      (node (ref "U2") (pin "88") (pinfunction "OE1_88") (pintype "input"))
    )
    (net (code "118") (name "unconnected-(U2Q-OE2-GCLK2-Pad90)") (class "Default")
      (node (ref "U2") (pin "90") (pinfunction "OE2-GCLK2_90") (pintype "input"))
    )
  )
)
